# untitled.net
KiCad netlist of a schematic drawn in EAGLE
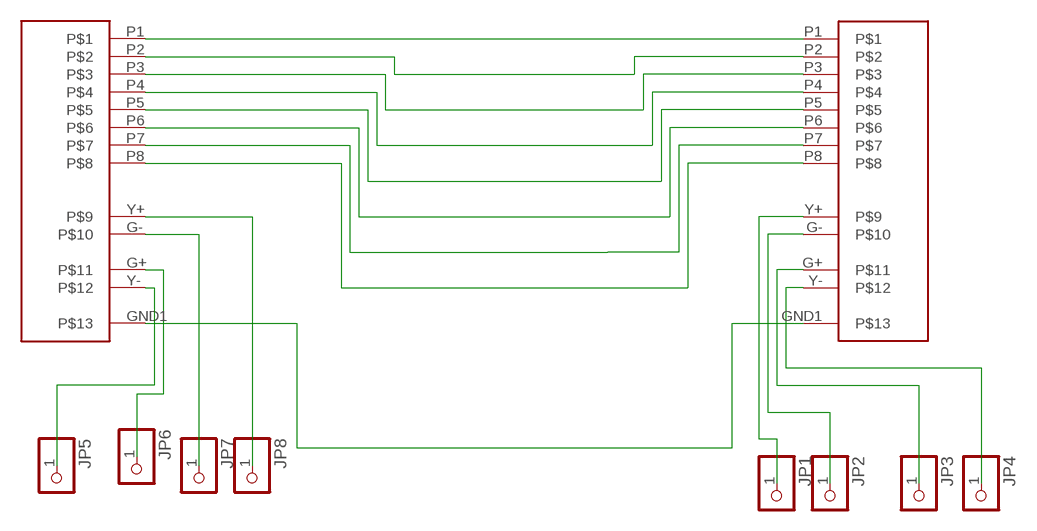
[diagram p0: schematic, sheet 1]

(export (version "E")
  (design (tool "Eeschema 10.0.6"))
  (components
    (comp (ref "JP1")
      (value "PINHD-1X1")
      (footprint "eagle-import:1X01")
      (libsource (lib "eagle-import") (part "PINHD-1X1"))
    )
    (comp (ref "JP2")
      (value "PINHD-1X1")
      (footprint "eagle-import:1X01")
      (libsource (lib "eagle-import") (part "PINHD-1X1"))
    )
    (comp (ref "JP3")
      (value "PINHD-1X1")
      (footprint "eagle-import:1X01")
      (libsource (lib "eagle-import") (part "PINHD-1X1"))
    )
    (comp (ref "JP4")
      (value "PINHD-1X1")
      (footprint "eagle-import:1X01")
      (libsource (lib "eagle-import") (part "PINHD-1X1"))
    )
    (comp (ref "JP5")
      (value "PINHD-1X1")
      (footprint "eagle-import:1X01")
      (libsource (lib "eagle-import") (part "PINHD-1X1"))
    )
    (comp (ref "JP6")
      (value "PINHD-1X1")
      (footprint "eagle-import:1X01")
      (libsource (lib "eagle-import") (part "PINHD-1X1"))
    )
    (comp (ref "JP7")
      (value "PINHD-1X1")
      (footprint "eagle-import:1X01")
      (libsource (lib "eagle-import") (part "PINHD-1X1"))
    )
    (comp (ref "JP8")
      (value "PINHD-1X1")
      (footprint "eagle-import:1X01")
      (libsource (lib "eagle-import") (part "PINHD-1X1"))
    )
    (comp (ref "U$14")
      (value "RJ-45_LEDS")
      (footprint "eagle-import:RJ-45_LEDS")
      (libsource (lib "eagle-import") (part "RJ-45_LEDS"))
    )
    (comp (ref "U$15")
      (value "RJ-45_LEDS")
      (footprint "eagle-import:RJ-45_LEDS")
      (libsource (lib "eagle-import") (part "RJ-45_LEDS"))
    )
  )
  (nets
    (net (code "1") (name "Net-(U$14-P$1)") (class "Default")
      (node (ref "U$14") (pin "P1") (pinfunction "P$1_P1") (pintype "bidirectional"))
      (node (ref "U$15") (pin "P1") (pinfunction "P$1_P1") (pintype "bidirectional"))
    )
    (net (code "2") (name "Net-(U$14-P$2)") (class "Default")
      (node (ref "U$14") (pin "P2") (pinfunction "P$2_P2") (pintype "bidirectional"))
      (node (ref "U$15") (pin "P2") (pinfunction "P$2_P2") (pintype "bidirectional"))
    )
    (net (code "3") (name "Net-(U$14-P$3)") (class "Default")
      (node (ref "U$14") (pin "P3") (pinfunction "P$3_P3") (pintype "bidirectional"))
      (node (ref "U$15") (pin "P3") (pinfunction "P$3_P3") (pintype "bidirectional"))
    )
    (net (code "4") (name "Net-(U$14-P$4)") (class "Default")
      (node (ref "U$14") (pin "P4") (pinfunction "P$4_P4") (pintype "bidirectional"))
      (node (ref "U$15") (pin "P4") (pinfunction "P$4_P4") (pintype "bidirectional"))
    )
    (net (code "5") (name "Net-(U$14-P$5)") (class "Default")
      (node (ref "U$14") (pin "P5") (pinfunction "P$5_P5") (pintype "bidirectional"))
      (node (ref "U$15") (pin "P5") (pinfunction "P$5_P5") (pintype "bidirectional"))
    )
    (net (code "6") (name "Net-(U$14-P$6)") (class "Default")
      (node (ref "U$14") (pin "P6") (pinfunction "P$6_P6") (pintype "bidirectional"))
      (node (ref "U$15") (pin "P6") (pinfunction "P$6_P6") (pintype "bidirectional"))
    )
    (net (code "7") (name "Net-(U$14-P$7)") (class "Default")
      (node (ref "U$14") (pin "P7") (pinfunction "P$7_P7") (pintype "bidirectional"))
      (node (ref "U$15") (pin "P7") (pinfunction "P$7_P7") (pintype "bidirectional"))
    )
    (net (code "8") (name "Net-(U$14-P$8)") (class "Default")
      (node (ref "U$14") (pin "P8") (pinfunction "P$8_P8") (pintype "bidirectional"))
      (node (ref "U$15") (pin "P8") (pinfunction "P$8_P8") (pintype "bidirectional"))
    )
    (net (code "9") (name "Net-(U$14-P$9)") (class "Default")
      (node (ref "JP8") (pin "1") (pinfunction "1_1") (pintype "passive"))
      (node (ref "U$14") (pin "Y+") (pinfunction "P$9_Y+") (pintype "power_in"))
    )
    (net (code "10") (name "Net-(U$14-P$10)") (class "Default")
      (node (ref "JP7") (pin "1") (pinfunction "1_1") (pintype "passive"))
      (node (ref "U$14") (pin "G-") (pinfunction "P$10_G-") (pintype "power_in"))
    )
    (net (code "11") (name "Net-(U$14-P$11)") (class "Default")
      (node (ref "JP6") (pin "1") (pinfunction "1_1") (pintype "passive"))
      (node (ref "U$14") (pin "G+") (pinfunction "P$11_G+") (pintype "power_in"))
    )
    (net (code "12") (name "Net-(U$14-P$12)") (class "Default")
      (node (ref "JP5") (pin "1") (pinfunction "1_1") (pintype "passive"))
      (node (ref "U$14") (pin "Y-") (pinfunction "P$12_Y-") (pintype "power_in"))
    )
    (net (code "13") (name "Net-(U$14-P$13)") (class "Default")
      (node (ref "U$14") (pin "GND1") (pinfunction "P$13_GND1") (pintype "power_in"))
      (node (ref "U$15") (pin "GND1") (pinfunction "P$13_GND1") (pintype "power_in"))
    )
    (net (code "14") (name "Net-(U$15-P$9)") (class "Default")
      (node (ref "JP1") (pin "1") (pinfunction "1_1") (pintype "passive"))
      (node (ref "U$15") (pin "Y+") (pinfunction "P$9_Y+") (pintype "power_in"))
    )
    (net (code "15") (name "Net-(U$15-P$10)") (class "Default")
      (node (ref "JP2") (pin "1") (pinfunction "1_1") (pintype "passive"))
      (node (ref "U$15") (pin "G-") (pinfunction "P$10_G-") (pintype "power_in"))
    )
    (net (code "16") (name "Net-(U$15-P$11)") (class "Default")
      (node (ref "JP3") (pin "1") (pinfunction "1_1") (pintype "passive"))
      (node (ref "U$15") (pin "G+") (pinfunction "P$11_G+") (pintype "power_in"))
    )
    (net (code "17") (name "Net-(U$15-P$12)") (class "Default")
      (node (ref "JP4") (pin "1") (pinfunction "1_1") (pintype "passive"))
      (node (ref "U$15") (pin "Y-") (pinfunction "P$12_Y-") (pintype "power_in"))
    )
  )
)
